# decoder.net
KiCad netlist of a schematic drawn in EAGLE
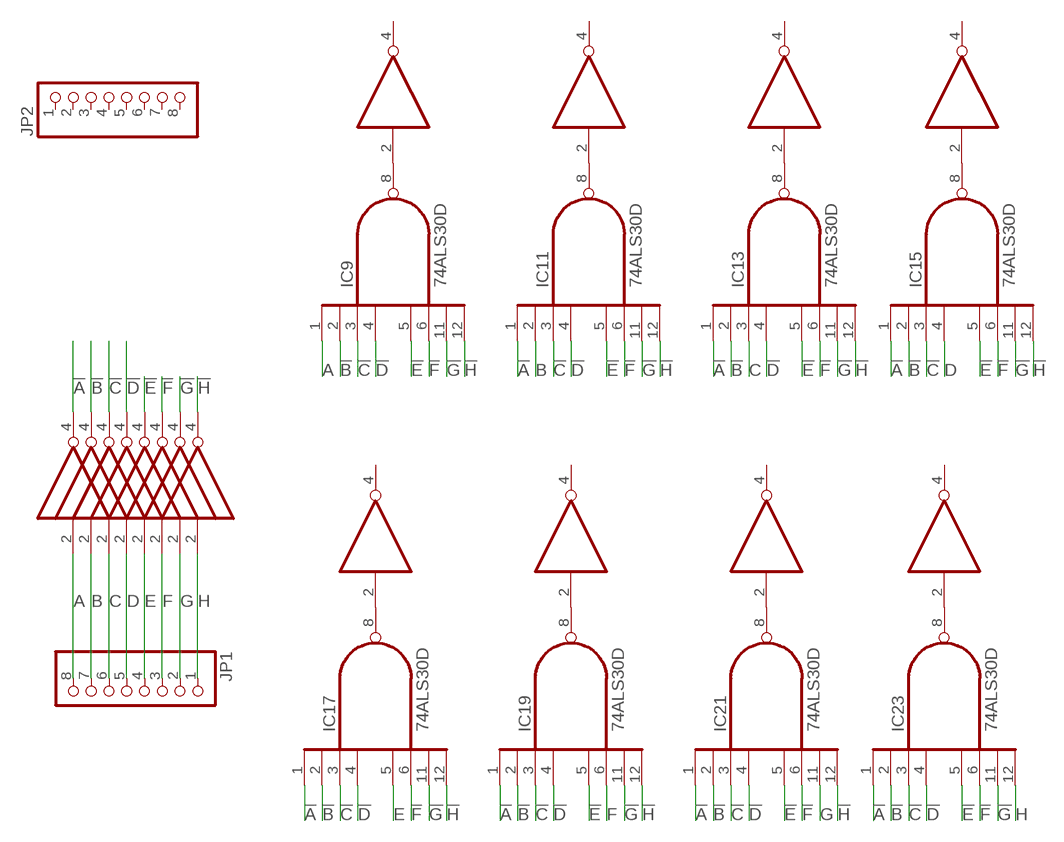
[diagram p0: schematic, sheet 1]

(export (version "E")
  (design (tool "Eeschema 10.0.6"))
  (components
    (comp (ref "IC1")
      (value "74AUC1G04DBV")
      (footprint "eagle-import:SOT23-5")
      (libsource (lib "eagle-import") (part "741G04DBVAUC"))
    )
    (comp (ref "IC2")
      (value "74AUC1G04DBV")
      (footprint "eagle-import:SOT23-5")
      (libsource (lib "eagle-import") (part "741G04DBVAUC"))
    )
    (comp (ref "IC3")
      (value "74AUC1G04DBV")
      (footprint "eagle-import:SOT23-5")
      (libsource (lib "eagle-import") (part "741G04DBVAUC"))
    )
    (comp (ref "IC4")
      (value "74AUC1G04DBV")
      (footprint "eagle-import:SOT23-5")
      (libsource (lib "eagle-import") (part "741G04DBVAUC"))
    )
    (comp (ref "IC5")
      (value "74AUC1G04DBV")
      (footprint "eagle-import:SOT23-5")
      (libsource (lib "eagle-import") (part "741G04DBVAUC"))
    )
    (comp (ref "IC6")
      (value "74AUC1G04DBV")
      (footprint "eagle-import:SOT23-5")
      (libsource (lib "eagle-import") (part "741G04DBVAUC"))
    )
    (comp (ref "IC7")
      (value "74AUC1G04DBV")
      (footprint "eagle-import:SOT23-5")
      (libsource (lib "eagle-import") (part "741G04DBVAUC"))
    )
    (comp (ref "IC8")
      (value "74AUC1G04DBV")
      (footprint "eagle-import:SOT23-5")
      (libsource (lib "eagle-import") (part "741G04DBVAUC"))
    )
    (comp (ref "IC9")
      (value "74ALS30D")
      (footprint "eagle-import:SO14")
      (libsource (lib "eagle-import") (part "7430DALS"))
    )
    (comp (ref "IC10")
      (value "74AUC1G04DBV")
      (footprint "eagle-import:SOT23-5")
      (libsource (lib "eagle-import") (part "741G04DBVAUC"))
    )
    (comp (ref "IC11")
      (value "74ALS30D")
      (footprint "eagle-import:SO14")
      (libsource (lib "eagle-import") (part "7430DALS"))
    )
    (comp (ref "IC12")
      (value "74AUC1G04DBV")
      (footprint "eagle-import:SOT23-5")
      (libsource (lib "eagle-import") (part "741G04DBVAUC"))
    )
    (comp (ref "IC13")
      (value "74ALS30D")
      (footprint "eagle-import:SO14")
      (libsource (lib "eagle-import") (part "7430DALS"))
    )
    (comp (ref "IC14")
      (value "74AUC1G04DBV")
      (footprint "eagle-import:SOT23-5")
      (libsource (lib "eagle-import") (part "741G04DBVAUC"))
    )
    (comp (ref "IC15")
      (value "74ALS30D")
      (footprint "eagle-import:SO14")
      (libsource (lib "eagle-import") (part "7430DALS"))
    )
    (comp (ref "IC16")
      (value "74AUC1G04DBV")
      (footprint "eagle-import:SOT23-5")
      (libsource (lib "eagle-import") (part "741G04DBVAUC"))
    )
    (comp (ref "IC17")
      (value "74ALS30D")
      (footprint "eagle-import:SO14")
      (libsource (lib "eagle-import") (part "7430DALS"))
    )
    (comp (ref "IC18")
      (value "74AUC1G04DBV")
      (footprint "eagle-import:SOT23-5")
      (libsource (lib "eagle-import") (part "741G04DBVAUC"))
    )
    (comp (ref "IC19")
      (value "74ALS30D")
      (footprint "eagle-import:SO14")
      (libsource (lib "eagle-import") (part "7430DALS"))
    )
    (comp (ref "IC20")
      (value "74AUC1G04DBV")
      (footprint "eagle-import:SOT23-5")
      (libsource (lib "eagle-import") (part "741G04DBVAUC"))
    )
    (comp (ref "IC21")
      (value "74ALS30D")
      (footprint "eagle-import:SO14")
      (libsource (lib "eagle-import") (part "7430DALS"))
    )
    (comp (ref "IC22")
      (value "74AUC1G04DBV")
      (footprint "eagle-import:SOT23-5")
      (libsource (lib "eagle-import") (part "741G04DBVAUC"))
    )
    (comp (ref "IC23")
      (value "74ALS30D")
      (footprint "eagle-import:SO14")
      (libsource (lib "eagle-import") (part "7430DALS"))
    )
    (comp (ref "IC24")
      (value "74AUC1G04DBV")
      (footprint "eagle-import:SOT23-5")
      (libsource (lib "eagle-import") (part "741G04DBVAUC"))
    )
    (comp (ref "JP1")
      (value "PINHD-1X8")
      (footprint "eagle-import:1X08")
      (libsource (lib "eagle-import") (part "PINHD-1X8"))
    )
    (comp (ref "JP2")
      (value "PINHD-1X8")
      (footprint "eagle-import:1X08")
      (libsource (lib "eagle-import") (part "PINHD-1X8"))
    )
  )
  (nets
    (net (code "1") (name "/A") (class "Default")
      (node (ref "IC1") (pin "2") (pinfunction "I_2") (pintype "input"))
      (node (ref "IC9") (pin "1") (pinfunction "I0_1") (pintype "input"))
      (node (ref "JP1") (pin "8") (pinfunction "8_8") (pintype "passive"))
    )
    (net (code "2") (name "/B") (class "Default")
      (node (ref "IC11") (pin "2") (pinfunction "I1_2") (pintype "input"))
      (node (ref "IC2") (pin "2") (pinfunction "I_2") (pintype "input"))
      (node (ref "JP1") (pin "7") (pinfunction "7_7") (pintype "passive"))
    )
    (net (code "3") (name "/C") (class "Default")
      (node (ref "IC13") (pin "3") (pinfunction "I2_3") (pintype "input"))
      (node (ref "IC3") (pin "2") (pinfunction "I_2") (pintype "input"))
      (node (ref "JP1") (pin "6") (pinfunction "6_6") (pintype "passive"))
    )
    (net (code "4") (name "/D") (class "Default")
      (node (ref "IC15") (pin "4") (pinfunction "I3_4") (pintype "input"))
      (node (ref "IC4") (pin "2") (pinfunction "I_2") (pintype "input"))
      (node (ref "JP1") (pin "5") (pinfunction "5_5") (pintype "passive"))
    )
    (net (code "5") (name "/E") (class "Default")
      (node (ref "IC17") (pin "5") (pinfunction "I4_5") (pintype "input"))
      (node (ref "IC5") (pin "2") (pinfunction "I_2") (pintype "input"))
      (node (ref "JP1") (pin "4") (pinfunction "4_4") (pintype "passive"))
    )
    (net (code "6") (name "/F") (class "Default")
      (node (ref "IC19") (pin "6") (pinfunction "I5_6") (pintype "input"))
      (node (ref "IC6") (pin "2") (pinfunction "I_2") (pintype "input"))
      (node (ref "JP1") (pin "3") (pinfunction "3_3") (pintype "passive"))
    )
    (net (code "7") (name "/G") (class "Default")
      (node (ref "IC21") (pin "11") (pinfunction "I6_11") (pintype "input"))
      (node (ref "IC7") (pin "2") (pinfunction "I_2") (pintype "input"))
      (node (ref "JP1") (pin "2") (pinfunction "2_2") (pintype "passive"))
    )
    (net (code "8") (name "/H") (class "Default")
      (node (ref "IC23") (pin "12") (pinfunction "I7_12") (pintype "input"))
      (node (ref "IC8") (pin "2") (pinfunction "I_2") (pintype "input"))
      (node (ref "JP1") (pin "1") (pinfunction "1_1") (pintype "passive"))
    )
    (net (code "9") (name "/~{A}") (class "Default")
      (node (ref "IC1") (pin "4") (pinfunction "O_4") (pintype "output"))
      (node (ref "IC11") (pin "1") (pinfunction "I0_1") (pintype "input"))
      (node (ref "IC13") (pin "1") (pinfunction "I0_1") (pintype "input"))
      (node (ref "IC15") (pin "1") (pinfunction "I0_1") (pintype "input"))
      (node (ref "IC17") (pin "1") (pinfunction "I0_1") (pintype "input"))
      (node (ref "IC19") (pin "1") (pinfunction "I0_1") (pintype "input"))
      (node (ref "IC21") (pin "1") (pinfunction "I0_1") (pintype "input"))
      (node (ref "IC23") (pin "1") (pinfunction "I0_1") (pintype "input"))
    )
    (net (code "10") (name "/~{B}") (class "Default")
      (node (ref "IC13") (pin "2") (pinfunction "I1_2") (pintype "input"))
      (node (ref "IC15") (pin "2") (pinfunction "I1_2") (pintype "input"))
      (node (ref "IC17") (pin "2") (pinfunction "I1_2") (pintype "input"))
      (node (ref "IC19") (pin "2") (pinfunction "I1_2") (pintype "input"))
      (node (ref "IC2") (pin "4") (pinfunction "O_4") (pintype "output"))
      (node (ref "IC21") (pin "2") (pinfunction "I1_2") (pintype "input"))
      (node (ref "IC23") (pin "2") (pinfunction "I1_2") (pintype "input"))
      (node (ref "IC9") (pin "2") (pinfunction "I1_2") (pintype "input"))
    )
    (net (code "11") (name "/~{C}") (class "Default")
      (node (ref "IC11") (pin "3") (pinfunction "I2_3") (pintype "input"))
      (node (ref "IC15") (pin "3") (pinfunction "I2_3") (pintype "input"))
      (node (ref "IC17") (pin "3") (pinfunction "I2_3") (pintype "input"))
      (node (ref "IC19") (pin "3") (pinfunction "I2_3") (pintype "input"))
      (node (ref "IC21") (pin "3") (pinfunction "I2_3") (pintype "input"))
      (node (ref "IC23") (pin "3") (pinfunction "I2_3") (pintype "input"))
      (node (ref "IC3") (pin "4") (pinfunction "O_4") (pintype "output"))
      (node (ref "IC9") (pin "3") (pinfunction "I2_3") (pintype "input"))
    )
    (net (code "12") (name "/~{D}") (class "Default")
      (node (ref "IC11") (pin "4") (pinfunction "I3_4") (pintype "input"))
      (node (ref "IC13") (pin "4") (pinfunction "I3_4") (pintype "input"))
      (node (ref "IC17") (pin "4") (pinfunction "I3_4") (pintype "input"))
      (node (ref "IC19") (pin "4") (pinfunction "I3_4") (pintype "input"))
      (node (ref "IC21") (pin "4") (pinfunction "I3_4") (pintype "input"))
      (node (ref "IC23") (pin "4") (pinfunction "I3_4") (pintype "input"))
      (node (ref "IC4") (pin "4") (pinfunction "O_4") (pintype "output"))
      (node (ref "IC9") (pin "4") (pinfunction "I3_4") (pintype "input"))
    )
    (net (code "13") (name "/~{E}") (class "Default")
      (node (ref "IC11") (pin "5") (pinfunction "I4_5") (pintype "input"))
      (node (ref "IC13") (pin "5") (pinfunction "I4_5") (pintype "input"))
      (node (ref "IC15") (pin "5") (pinfunction "I4_5") (pintype "input"))
      (node (ref "IC19") (pin "5") (pinfunction "I4_5") (pintype "input"))
      (node (ref "IC21") (pin "5") (pinfunction "I4_5") (pintype "input"))
      (node (ref "IC23") (pin "5") (pinfunction "I4_5") (pintype "input"))
      (node (ref "IC5") (pin "4") (pinfunction "O_4") (pintype "output"))
      (node (ref "IC9") (pin "5") (pinfunction "I4_5") (pintype "input"))
    )
    (net (code "14") (name "/~{F}") (class "Default")
      (node (ref "IC11") (pin "6") (pinfunction "I5_6") (pintype "input"))
      (node (ref "IC13") (pin "6") (pinfunction "I5_6") (pintype "input"))
      (node (ref "IC15") (pin "6") (pinfunction "I5_6") (pintype "input"))
      (node (ref "IC17") (pin "6") (pinfunction "I5_6") (pintype "input"))
      (node (ref "IC21") (pin "6") (pinfunction "I5_6") (pintype "input"))
      (node (ref "IC23") (pin "6") (pinfunction "I5_6") (pintype "input"))
      (node (ref "IC6") (pin "4") (pinfunction "O_4") (pintype "output"))
      (node (ref "IC9") (pin "6") (pinfunction "I5_6") (pintype "input"))
    )
    (net (code "15") (name "/~{G}") (class "Default")
      (node (ref "IC11") (pin "11") (pinfunction "I6_11") (pintype "input"))
      (node (ref "IC13") (pin "11") (pinfunction "I6_11") (pintype "input"))
      (node (ref "IC15") (pin "11") (pinfunction "I6_11") (pintype "input"))
      (node (ref "IC17") (pin "11") (pinfunction "I6_11") (pintype "input"))
      (node (ref "IC19") (pin "11") (pinfunction "I6_11") (pintype "input"))
      (node (ref "IC23") (pin "11") (pinfunction "I6_11") (pintype "input"))
      (node (ref "IC7") (pin "4") (pinfunction "O_4") (pintype "output"))
      (node (ref "IC9") (pin "11") (pinfunction "I6_11") (pintype "input"))
    )
    (net (code "16") (name "/~{H}") (class "Default")
      (node (ref "IC11") (pin "12") (pinfunction "I7_12") (pintype "input"))
      (node (ref "IC13") (pin "12") (pinfunction "I7_12") (pintype "input"))
      (node (ref "IC15") (pin "12") (pinfunction "I7_12") (pintype "input"))
      (node (ref "IC17") (pin "12") (pinfunction "I7_12") (pintype "input"))
      (node (ref "IC19") (pin "12") (pinfunction "I7_12") (pintype "input"))
      (node (ref "IC21") (pin "12") (pinfunction "I7_12") (pintype "input"))
      (node (ref "IC8") (pin "4") (pinfunction "O_4") (pintype "output"))
      (node (ref "IC9") (pin "12") (pinfunction "I7_12") (pintype "input"))
    )
    (net (code "17") (name "Net-(IC10A-I)") (class "Default")
      (node (ref "IC10") (pin "2") (pinfunction "I_2") (pintype "input"))
      (node (ref "IC9") (pin "8") (pinfunction "O_8") (pintype "output"))
    )
    (net (code "18") (name "Net-(IC11A-O)") (class "Default")
      (node (ref "IC11") (pin "8") (pinfunction "O_8") (pintype "output"))
      (node (ref "IC12") (pin "2") (pinfunction "I_2") (pintype "input"))
    )
    (net (code "19") (name "Net-(IC13A-O)") (class "Default")
      (node (ref "IC13") (pin "8") (pinfunction "O_8") (pintype "output"))
      (node (ref "IC14") (pin "2") (pinfunction "I_2") (pintype "input"))
    )
    (net (code "20") (name "Net-(IC15A-O)") (class "Default")
      (node (ref "IC15") (pin "8") (pinfunction "O_8") (pintype "output"))
      (node (ref "IC16") (pin "2") (pinfunction "I_2") (pintype "input"))
    )
    (net (code "21") (name "Net-(IC17A-O)") (class "Default")
      (node (ref "IC17") (pin "8") (pinfunction "O_8") (pintype "output"))
      (node (ref "IC18") (pin "2") (pinfunction "I_2") (pintype "input"))
    )
    (net (code "22") (name "Net-(IC19A-O)") (class "Default")
      (node (ref "IC19") (pin "8") (pinfunction "O_8") (pintype "output"))
      (node (ref "IC20") (pin "2") (pinfunction "I_2") (pintype "input"))
    )
    (net (code "23") (name "Net-(IC21A-O)") (class "Default")
      (node (ref "IC21") (pin "8") (pinfunction "O_8") (pintype "output"))
      (node (ref "IC22") (pin "2") (pinfunction "I_2") (pintype "input"))
    )
    (net (code "24") (name "Net-(IC23A-O)") (class "Default")
      (node (ref "IC23") (pin "8") (pinfunction "O_8") (pintype "output"))
      (node (ref "IC24") (pin "2") (pinfunction "I_2") (pintype "input"))
    )
    (net (code "25") (name "unconnected-(IC10A-O-Pad4)") (class "Default")
      (node (ref "IC10") (pin "4") (pinfunction "O_4") (pintype "output"))
    )
    (net (code "26") (name "unconnected-(IC12A-O-Pad4)") (class "Default")
      (node (ref "IC12") (pin "4") (pinfunction "O_4") (pintype "output"))
    )
    (net (code "27") (name "unconnected-(IC14A-O-Pad4)") (class "Default")
      (node (ref "IC14") (pin "4") (pinfunction "O_4") (pintype "output"))
    )
    (net (code "28") (name "unconnected-(IC16A-O-Pad4)") (class "Default")
      (node (ref "IC16") (pin "4") (pinfunction "O_4") (pintype "output"))
    )
    (net (code "29") (name "unconnected-(IC18A-O-Pad4)") (class "Default")
      (node (ref "IC18") (pin "4") (pinfunction "O_4") (pintype "output"))
    )
    (net (code "30") (name "unconnected-(IC20A-O-Pad4)") (class "Default")
      (node (ref "IC20") (pin "4") (pinfunction "O_4") (pintype "output"))
    )
    (net (code "31") (name "unconnected-(IC22A-O-Pad4)") (class "Default")
      (node (ref "IC22") (pin "4") (pinfunction "O_4") (pintype "output"))
    )
    (net (code "32") (name "unconnected-(IC24A-O-Pad4)") (class "Default")
      (node (ref "IC24") (pin "4") (pinfunction "O_4") (pintype "output"))
    )
    (net (code "33") (name "unconnected-(JP2-Pad1)") (class "Default")
      (node (ref "JP2") (pin "1") (pinfunction "1_1") (pintype "passive"))
    )
    (net (code "34") (name "unconnected-(JP2-Pad2)") (class "Default")
      (node (ref "JP2") (pin "2") (pinfunction "2_2") (pintype "passive"))
    )
    (net (code "35") (name "unconnected-(JP2-Pad3)") (class "Default")
      (node (ref "JP2") (pin "3") (pinfunction "3_3") (pintype "passive"))
    )
    (net (code "36") (name "unconnected-(JP2-Pad4)") (class "Default")
      (node (ref "JP2") (pin "4") (pinfunction "4_4") (pintype "passive"))
    )
    (net (code "37") (name "unconnected-(JP2-Pad5)") (class "Default")
      (node (ref "JP2") (pin "5") (pinfunction "5_5") (pintype "passive"))
    )
    (net (code "38") (name "unconnected-(JP2-Pad6)") (class "Default")
      (node (ref "JP2") (pin "6") (pinfunction "6_6") (pintype "passive"))
    )
    (net (code "39") (name "unconnected-(JP2-Pad7)") (class "Default")
      (node (ref "JP2") (pin "7") (pinfunction "7_7") (pintype "passive"))
    )
    (net (code "40") (name "unconnected-(JP2-Pad8)") (class "Default")
      (node (ref "JP2") (pin "8") (pinfunction "8_8") (pintype "passive"))
    )
  )
)
